# v2_phys.net
KiCad netlist of a schematic drawn in EAGLE
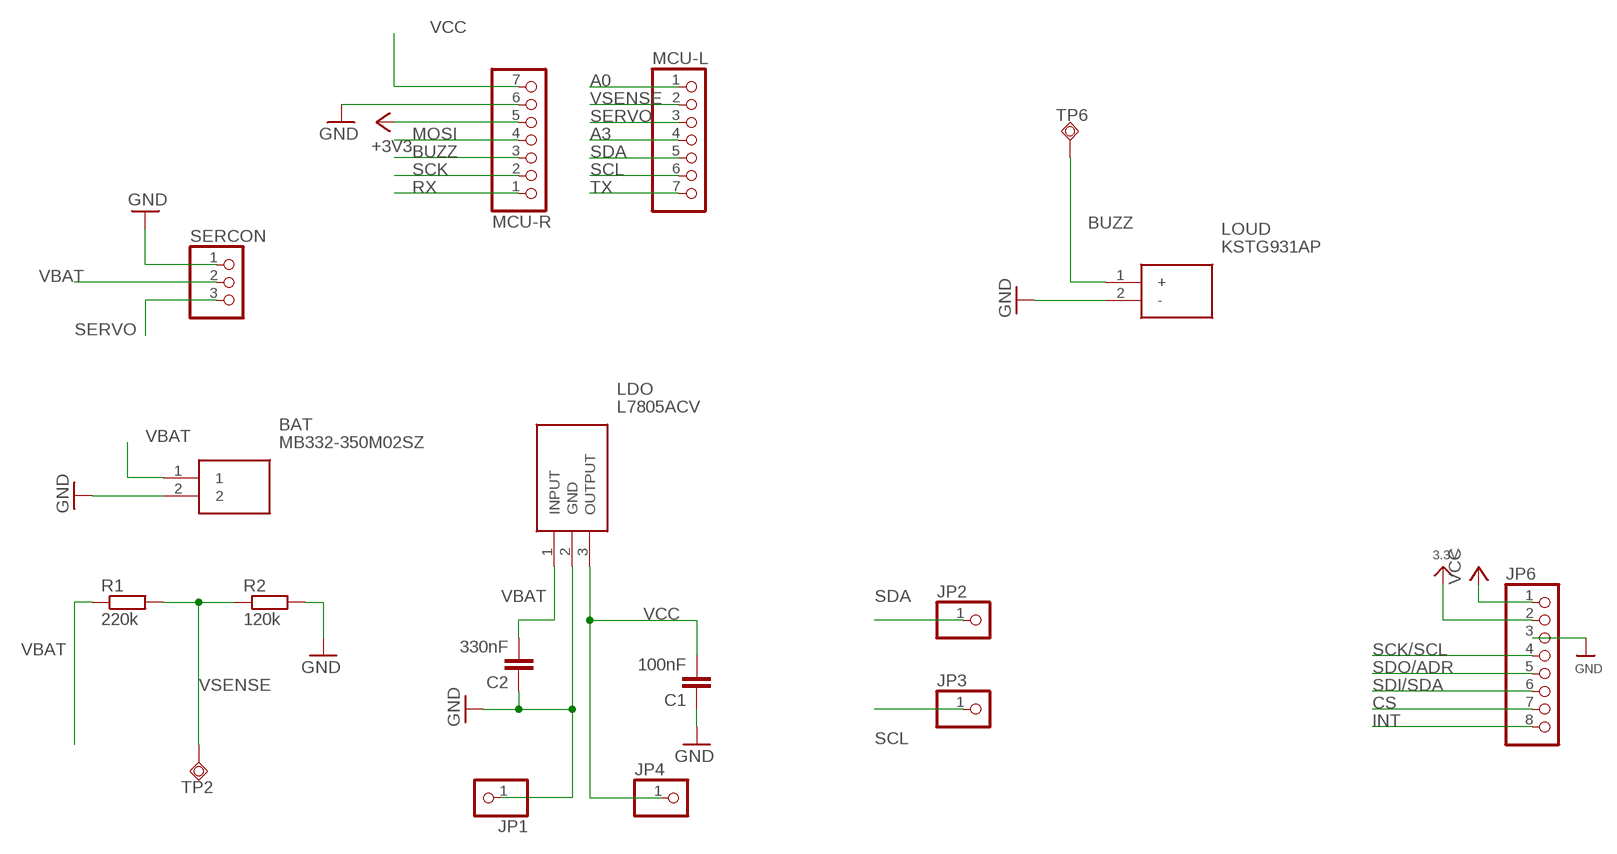
[diagram p0: schematic, sheet 1]

(export (version "E")
  (design (tool "Eeschema 10.0.6"))
  (components
    (comp (ref "BAT")
      (value "MB332-350M02SZ")
      (footprint "eagle-import:MB332350M02SZ")
      (fields (field (name "RS_PART_NUMBER") "7901149"))
      (libsource (lib "eagle-import") (part "MB332-350M02SZ"))
    )
    (comp (ref "C1")
      (value "100nF")
      (footprint "eagle-import:C025-024X044")
      (libsource (lib "eagle-import") (part "C-EU025-024X044"))
    )
    (comp (ref "C2")
      (value "330nF")
      (footprint "eagle-import:C025-024X044")
      (libsource (lib "eagle-import") (part "C-EU025-024X044"))
    )
    (comp (ref "JP1")
      (value "PINHD-1X1")
      (footprint "eagle-import:1X01")
      (libsource (lib "eagle-import") (part "PINHD-1X1"))
    )
    (comp (ref "JP2")
      (value "PINHD-1X1")
      (footprint "eagle-import:1X01")
      (libsource (lib "eagle-import") (part "PINHD-1X1"))
    )
    (comp (ref "JP3")
      (value "PINHD-1X1")
      (footprint "eagle-import:1X01")
      (libsource (lib "eagle-import") (part "PINHD-1X1"))
    )
    (comp (ref "JP4")
      (value "PINHD-1X1")
      (footprint "eagle-import:1X01")
      (libsource (lib "eagle-import") (part "PINHD-1X1"))
    )
    (comp (ref "JP6")
      (value "HEADER-1X870MIL")
      (footprint "eagle-import:1X08_ROUND_70")
      (libsource (lib "eagle-import") (part "HEADER-1X870MIL"))
    )
    (comp (ref "LDO")
      (value "L7805ACV")
      (footprint "eagle-import:TO255P460X1020X2008-3P")
      (fields (field (name "RS_PART_NUMBER") "2988508P"))
      (libsource (lib "eagle-import") (part "L7805ACV"))
    )
    (comp (ref "LOUD")
      (value "KSTG931AP")
      (footprint "eagle-import:CAPPRD400W70D900H500")
      (libsource (lib "eagle-import") (part "KSTG931AP"))
    )
    (comp (ref "MCU-L")
      (value "HEADER-1X7")
      (footprint "eagle-import:1X07_OVAL")
      (libsource (lib "eagle-import") (part "HEADER-1X7"))
    )
    (comp (ref "MCU-R")
      (value "HEADER-1X7")
      (footprint "eagle-import:1X07_OVAL")
      (libsource (lib "eagle-import") (part "HEADER-1X7"))
    )
    (comp (ref "R1")
      (value "220k")
      (footprint "eagle-import:0204V")
      (libsource (lib "eagle-import") (part "R-EU_0204/2V"))
    )
    (comp (ref "R2")
      (value "120k")
      (footprint "eagle-import:0204V")
      (libsource (lib "eagle-import") (part "R-EU_0204/2V"))
    )
    (comp (ref "SERCON")
      (value "PINHD-1X3")
      (footprint "eagle-import:1X03")
      (libsource (lib "eagle-import") (part "PINHD-1X3"))
    )
    (comp (ref "TP2")
      (value "TPSQB2,54")
      (footprint "eagle-import:B2,54")
      (libsource (lib "eagle-import") (part "TPSQB2,54"))
    )
    (comp (ref "TP6")
      (value "TPSQB2,54")
      (footprint "eagle-import:B2,54")
      (libsource (lib "eagle-import") (part "TPSQB2,54"))
    )
  )
  (nets
    (net (code "1") (name "+3V3") (class "Default")
      (node (ref "MCU-R") (pin "5") (pinfunction "5_5") (pintype "passive"))
    )
    (net (code "2") (name "/A0") (class "Default")
      (node (ref "MCU-L") (pin "1") (pinfunction "1_1") (pintype "passive"))
    )
    (net (code "3") (name "/A3") (class "Default")
      (node (ref "MCU-L") (pin "4") (pinfunction "4_4") (pintype "passive"))
    )
    (net (code "4") (name "/BUZZ") (class "Default")
      (node (ref "LOUD") (pin "1") (pinfunction "+_1") (pintype "bidirectional"))
      (node (ref "MCU-R") (pin "3") (pinfunction "3_3") (pintype "passive"))
      (node (ref "TP6") (pin "TP") (pinfunction "TP_TP") (pintype "input"))
    )
    (net (code "5") (name "/CS") (class "Default")
      (node (ref "JP6") (pin "7") (pinfunction "7_7") (pintype "passive"))
    )
    (net (code "6") (name "/INT") (class "Default")
      (node (ref "JP6") (pin "8") (pinfunction "8_8") (pintype "passive"))
    )
    (net (code "7") (name "/MOSI") (class "Default")
      (node (ref "MCU-R") (pin "4") (pinfunction "4_4") (pintype "passive"))
    )
    (net (code "8") (name "/RX") (class "Default")
      (node (ref "MCU-R") (pin "1") (pinfunction "1_1") (pintype "passive"))
    )
    (net (code "9") (name "/SCK") (class "Default")
      (node (ref "MCU-R") (pin "2") (pinfunction "2_2") (pintype "passive"))
    )
    (net (code "10") (name "/SCK{slash}SCL") (class "Default")
      (node (ref "JP6") (pin "4") (pinfunction "4_4") (pintype "passive"))
    )
    (net (code "11") (name "/SCL") (class "Default")
      (node (ref "JP3") (pin "1") (pinfunction "1_1") (pintype "passive"))
      (node (ref "MCU-L") (pin "6") (pinfunction "6_6") (pintype "passive"))
    )
    (net (code "12") (name "/SDA") (class "Default")
      (node (ref "JP2") (pin "1") (pinfunction "1_1") (pintype "passive"))
      (node (ref "MCU-L") (pin "5") (pinfunction "5_5") (pintype "passive"))
    )
    (net (code "13") (name "/SDI{slash}SDA") (class "Default")
      (node (ref "JP6") (pin "6") (pinfunction "6_6") (pintype "passive"))
    )
    (net (code "14") (name "/SDO{slash}ADR") (class "Default")
      (node (ref "JP6") (pin "5") (pinfunction "5_5") (pintype "passive"))
    )
    (net (code "15") (name "/SERVO") (class "Default")
      (node (ref "MCU-L") (pin "3") (pinfunction "3_3") (pintype "passive"))
      (node (ref "SERCON") (pin "3") (pinfunction "3_3") (pintype "passive"))
    )
    (net (code "16") (name "/TX") (class "Default")
      (node (ref "MCU-L") (pin "7") (pinfunction "7_7") (pintype "passive"))
    )
    (net (code "17") (name "/VBAT") (class "Default")
      (node (ref "BAT") (pin "1") (pinfunction "1_1") (pintype "bidirectional"))
      (node (ref "C2") (pin "2") (pinfunction "2_2") (pintype "passive"))
      (node (ref "LDO") (pin "1") (pinfunction "INPUT_1") (pintype "bidirectional"))
      (node (ref "R1") (pin "1") (pinfunction "1_1") (pintype "passive"))
      (node (ref "SERCON") (pin "2") (pinfunction "2_2") (pintype "passive"))
    )
    (net (code "18") (name "/VSENSE") (class "Default")
      (node (ref "MCU-L") (pin "2") (pinfunction "2_2") (pintype "passive"))
      (node (ref "R1") (pin "2") (pinfunction "2_2") (pintype "passive"))
      (node (ref "R2") (pin "1") (pinfunction "1_1") (pintype "passive"))
      (node (ref "TP2") (pin "TP") (pinfunction "TP_TP") (pintype "input"))
    )
    (net (code "19") (name "3.3V") (class "Default")
      (node (ref "JP6") (pin "2") (pinfunction "2_2") (pintype "passive"))
    )
    (net (code "20") (name "GND") (class "Default")
      (node (ref "BAT") (pin "2") (pinfunction "2_2") (pintype "bidirectional"))
      (node (ref "C1") (pin "1") (pinfunction "1_1") (pintype "passive"))
      (node (ref "C2") (pin "1") (pinfunction "1_1") (pintype "passive"))
      (node (ref "JP1") (pin "1") (pinfunction "1_1") (pintype "passive"))
      (node (ref "JP6") (pin "3") (pinfunction "3_3") (pintype "passive"))
      (node (ref "LDO") (pin "2") (pinfunction "GND_2") (pintype "bidirectional"))
      (node (ref "LOUD") (pin "2") (pinfunction "-_2") (pintype "bidirectional"))
      (node (ref "MCU-R") (pin "6") (pinfunction "6_6") (pintype "passive"))
      (node (ref "R2") (pin "2") (pinfunction "2_2") (pintype "passive"))
      (node (ref "SERCON") (pin "1") (pinfunction "1_1") (pintype "passive"))
    )
    (net (code "21") (name "VCC") (class "Default")
      (node (ref "C1") (pin "2") (pinfunction "2_2") (pintype "passive"))
      (node (ref "JP4") (pin "1") (pinfunction "1_1") (pintype "passive"))
      (node (ref "JP6") (pin "1") (pinfunction "1_1") (pintype "passive"))
      (node (ref "LDO") (pin "3") (pinfunction "OUTPUT_3") (pintype "bidirectional"))
      (node (ref "MCU-R") (pin "7") (pinfunction "7_7") (pintype "passive"))
    )
  )
)
